# tpa6120a2_headamp.net
KiCad netlist of a schematic drawn in EAGLE
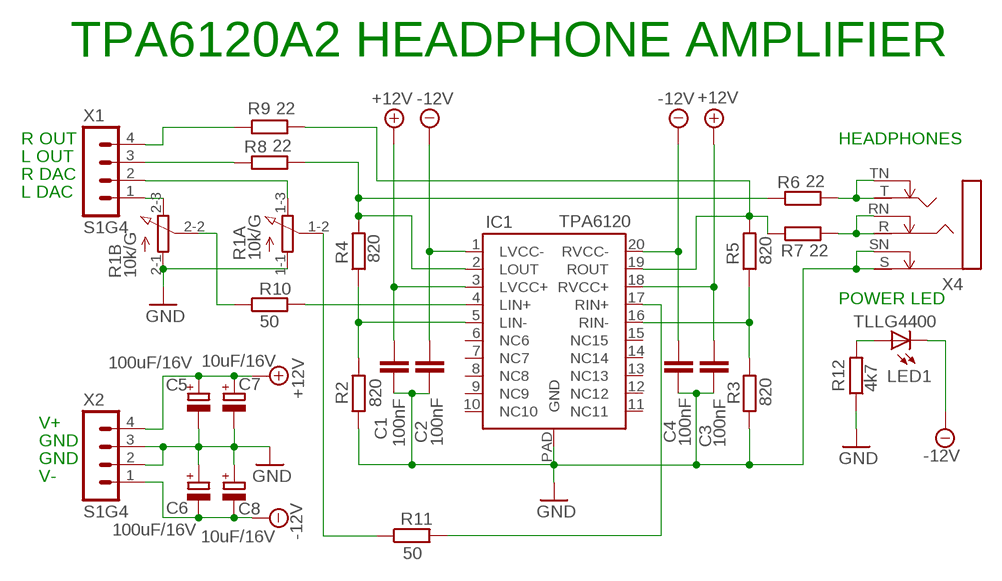
[diagram p0: schematic, sheet 1]

(export (version "E")
  (design (tool "Eeschema 10.0.6"))
  (components
    (comp (ref "C1")
      (value "100nF")
      (footprint "eagle-import:C1206")
      (libsource (lib "eagle-import") (part "C-EUC1206"))
    )
    (comp (ref "C2")
      (value "100nF")
      (footprint "eagle-import:C1206")
      (libsource (lib "eagle-import") (part "C-EUC1206"))
    )
    (comp (ref "C3")
      (value "100nF")
      (footprint "eagle-import:C1206")
      (libsource (lib "eagle-import") (part "C-EUC1206"))
    )
    (comp (ref "C4")
      (value "100nF")
      (footprint "eagle-import:C1206")
      (libsource (lib "eagle-import") (part "C-EUC1206"))
    )
    (comp (ref "C5")
      (value "100uF/16V")
      (footprint "eagle-import:SMC_D")
      (libsource (lib "eagle-import") (part "CPOL-EUSMCD"))
    )
    (comp (ref "C6")
      (value "100uF/16V")
      (footprint "eagle-import:SMC_D")
      (libsource (lib "eagle-import") (part "CPOL-EUSMCD"))
    )
    (comp (ref "C7")
      (value "10uF/16V")
      (footprint "eagle-import:SMC_C")
      (libsource (lib "eagle-import") (part "CPOL-EUSMCC"))
    )
    (comp (ref "C8")
      (value "10uF/16V")
      (footprint "eagle-import:SMC_C")
      (libsource (lib "eagle-import") (part "CPOL-EUSMCC"))
    )
    (comp (ref "IC1")
      (value "TPA6120")
      (footprint "eagle-import:SO20POWERPAD")
      (libsource (lib "eagle-import") (part "TPA6120"))
    )
    (comp (ref "LED1")
      (value "TLLG4400")
      (footprint "eagle-import:LED3MM")
      (fields (field (name "MF") "VISHAY SEMICONDUCTOR"))
      (libsource (lib "eagle-import") (part "TLLG4400"))
    )
    (comp (ref "R1")
      (value "10k/G")
      (footprint "eagle-import:ALPS-RK27-DUAL")
      (libsource (lib "eagle-import") (part "ALPS-RK27-DUAL"))
    )
    (comp (ref "R2")
      (value "820")
      (footprint "eagle-import:R1206")
      (libsource (lib "eagle-import") (part "R-EU_R1206"))
    )
    (comp (ref "R3")
      (value "820")
      (footprint "eagle-import:R1206")
      (libsource (lib "eagle-import") (part "R-EU_R1206"))
    )
    (comp (ref "R4")
      (value "820")
      (footprint "eagle-import:R1206")
      (libsource (lib "eagle-import") (part "R-EU_R1206"))
    )
    (comp (ref "R5")
      (value "820")
      (footprint "eagle-import:R1206")
      (libsource (lib "eagle-import") (part "R-EU_R1206"))
    )
    (comp (ref "R6")
      (value "22")
      (footprint "eagle-import:R1206")
      (libsource (lib "eagle-import") (part "R-EU_R1206"))
    )
    (comp (ref "R7")
      (value "22")
      (footprint "eagle-import:R1206")
      (libsource (lib "eagle-import") (part "R-EU_R1206"))
    )
    (comp (ref "R8")
      (value "22")
      (footprint "eagle-import:R1206")
      (libsource (lib "eagle-import") (part "R-EU_R1206"))
    )
    (comp (ref "R9")
      (value "22")
      (footprint "eagle-import:R1206")
      (libsource (lib "eagle-import") (part "R-EU_R1206"))
    )
    (comp (ref "R10")
      (value "50")
      (footprint "eagle-import:R1206")
      (libsource (lib "eagle-import") (part "R-EU_R1206"))
    )
    (comp (ref "R11")
      (value "50")
      (footprint "eagle-import:R1206")
      (libsource (lib "eagle-import") (part "R-EU_R1206"))
    )
    (comp (ref "R12")
      (value "4k7")
      (footprint "eagle-import:R1206")
      (libsource (lib "eagle-import") (part "R-EU_R1206"))
    )
    (comp (ref "X1")
      (value "S1G4")
      (footprint "eagle-import:MA04-1")
      (libsource (lib "eagle-import") (part "MA04-1"))
    )
    (comp (ref "X2")
      (value "S1G4")
      (footprint "eagle-import:MA04-1")
      (libsource (lib "eagle-import") (part "MA04-1"))
    )
    (comp (ref "X4")
      (value "NMJ6HCD2")
      (footprint "eagle-import:NMJ6HCD2")
      (libsource (lib "eagle-import") (part "NMJ6HCD2"))
    )
  )
  (nets
    (net (code "1") (name "+12V") (class "Default")
      (node (ref "C1") (pin "1") (pinfunction "1_1") (pintype "passive"))
      (node (ref "C3") (pin "1") (pinfunction "1_1") (pintype "passive"))
      (node (ref "C5") (pin "+") (pinfunction "+_+") (pintype "passive"))
      (node (ref "C7") (pin "+") (pinfunction "+_+") (pintype "passive"))
      (node (ref "IC1") (pin "18") (pinfunction "RVCC+_18") (pintype "power_in"))
      (node (ref "IC1") (pin "3") (pinfunction "LVCC+_3") (pintype "power_in"))
      (node (ref "X2") (pin "4") (pinfunction "4_4") (pintype "passive"))
    )
    (net (code "2") (name "-12V") (class "Default")
      (node (ref "C2") (pin "1") (pinfunction "1_1") (pintype "passive"))
      (node (ref "C4") (pin "1") (pinfunction "1_1") (pintype "passive"))
      (node (ref "C6") (pin "-") (pinfunction "-_-") (pintype "passive"))
      (node (ref "C8") (pin "-") (pinfunction "-_-") (pintype "passive"))
      (node (ref "IC1") (pin "1") (pinfunction "LVCC-_1") (pintype "power_in"))
      (node (ref "IC1") (pin "20") (pinfunction "RVCC-_20") (pintype "power_in"))
      (node (ref "LED1") (pin "K") (pinfunction "C_K") (pintype "passive"))
      (node (ref "X2") (pin "1") (pinfunction "1_1") (pintype "passive"))
    )
    (net (code "3") (name "GND") (class "Default")
      (node (ref "C1") (pin "2") (pinfunction "2_2") (pintype "passive"))
      (node (ref "C2") (pin "2") (pinfunction "2_2") (pintype "passive"))
      (node (ref "C3") (pin "2") (pinfunction "2_2") (pintype "passive"))
      (node (ref "C4") (pin "2") (pinfunction "2_2") (pintype "passive"))
      (node (ref "C5") (pin "-") (pinfunction "-_-") (pintype "passive"))
      (node (ref "C6") (pin "+") (pinfunction "+_+") (pintype "passive"))
      (node (ref "C7") (pin "-") (pinfunction "-_-") (pintype "passive"))
      (node (ref "C8") (pin "+") (pinfunction "+_+") (pintype "passive"))
      (node (ref "IC1") (pin "PAD") (pinfunction "GND_PAD") (pintype "power_in"))
      (node (ref "R1") (pin "1-1") (pinfunction "1_1-1") (pintype "passive"))
      (node (ref "R1") (pin "2-1") (pinfunction "1_2-1") (pintype "passive"))
      (node (ref "R12") (pin "1") (pinfunction "1_1") (pintype "passive"))
      (node (ref "R2") (pin "1") (pinfunction "1_1") (pintype "passive"))
      (node (ref "R3") (pin "1") (pinfunction "1_1") (pintype "passive"))
      (node (ref "X2") (pin "2") (pinfunction "2_2") (pintype "passive"))
      (node (ref "X2") (pin "3") (pinfunction "3_3") (pintype "passive"))
      (node (ref "X4") (pin "S") (pinfunction "S_S") (pintype "passive"))
      (node (ref "X4") (pin "SN") (pinfunction "SN_SN") (pintype "passive"))
    )
    (net (code "4") (name "Net-(IC1-LIN+)") (class "Default")
      (node (ref "IC1") (pin "4") (pinfunction "LIN+_4") (pintype "input"))
      (node (ref "R10") (pin "2") (pinfunction "2_2") (pintype "passive"))
    )
    (net (code "5") (name "Net-(IC1-LIN-)") (class "Default")
      (node (ref "IC1") (pin "5") (pinfunction "LIN-_5") (pintype "input"))
      (node (ref "R2") (pin "2") (pinfunction "2_2") (pintype "passive"))
      (node (ref "R4") (pin "1") (pinfunction "1_1") (pintype "passive"))
    )
    (net (code "6") (name "Net-(IC1-LOUT)") (class "Default")
      (node (ref "IC1") (pin "2") (pinfunction "LOUT_2") (pintype "output"))
      (node (ref "R4") (pin "2") (pinfunction "2_2") (pintype "passive"))
      (node (ref "R6") (pin "1") (pinfunction "1_1") (pintype "passive"))
      (node (ref "R8") (pin "2") (pinfunction "2_2") (pintype "passive"))
    )
    (net (code "7") (name "Net-(IC1-RIN+)") (class "Default")
      (node (ref "IC1") (pin "17") (pinfunction "RIN+_17") (pintype "input"))
      (node (ref "R11") (pin "2") (pinfunction "2_2") (pintype "passive"))
    )
    (net (code "8") (name "Net-(IC1-RIN-)") (class "Default")
      (node (ref "IC1") (pin "16") (pinfunction "RIN-_16") (pintype "input"))
      (node (ref "R3") (pin "2") (pinfunction "2_2") (pintype "passive"))
      (node (ref "R5") (pin "1") (pinfunction "1_1") (pintype "passive"))
    )
    (net (code "9") (name "Net-(IC1-ROUT)") (class "Default")
      (node (ref "IC1") (pin "19") (pinfunction "ROUT_19") (pintype "output"))
      (node (ref "R5") (pin "2") (pinfunction "2_2") (pintype "passive"))
      (node (ref "R7") (pin "1") (pinfunction "1_1") (pintype "passive"))
      (node (ref "R9") (pin "2") (pinfunction "2_2") (pintype "passive"))
    )
    (net (code "10") (name "Net-(LED1-PadA)") (class "Default")
      (node (ref "LED1") (pin "A") (pinfunction "A_A") (pintype "passive"))
      (node (ref "R12") (pin "2") (pinfunction "2_2") (pintype "passive"))
    )
    (net (code "11") (name "Net-(R1A-2)") (class "Default")
      (node (ref "R1") (pin "1-2") (pinfunction "2_1-2") (pintype "passive"))
      (node (ref "R11") (pin "1") (pinfunction "1_1") (pintype "passive"))
    )
    (net (code "12") (name "Net-(R1A-3)") (class "Default")
      (node (ref "R1") (pin "1-3") (pinfunction "3_1-3") (pintype "passive"))
      (node (ref "X1") (pin "2") (pinfunction "2_2") (pintype "passive"))
    )
    (net (code "13") (name "Net-(R1B-2)") (class "Default")
      (node (ref "R1") (pin "2-2") (pinfunction "2_2-2") (pintype "passive"))
      (node (ref "R10") (pin "1") (pinfunction "1_1") (pintype "passive"))
    )
    (net (code "14") (name "Net-(R1B-3)") (class "Default")
      (node (ref "R1") (pin "2-3") (pinfunction "3_2-3") (pintype "passive"))
      (node (ref "X1") (pin "1") (pinfunction "1_1") (pintype "passive"))
    )
    (net (code "15") (name "Net-(R6-Pad2)") (class "Default")
      (node (ref "R6") (pin "2") (pinfunction "2_2") (pintype "passive"))
      (node (ref "X4") (pin "T") (pinfunction "T_T") (pintype "passive"))
      (node (ref "X4") (pin "TN") (pinfunction "TN_TN") (pintype "passive"))
    )
    (net (code "16") (name "Net-(R7-Pad2)") (class "Default")
      (node (ref "R7") (pin "2") (pinfunction "2_2") (pintype "passive"))
      (node (ref "X4") (pin "R") (pinfunction "R_R") (pintype "passive"))
      (node (ref "X4") (pin "RN") (pinfunction "RN_RN") (pintype "passive"))
    )
    (net (code "17") (name "Net-(R8-Pad1)") (class "Default")
      (node (ref "R8") (pin "1") (pinfunction "1_1") (pintype "passive"))
      (node (ref "X1") (pin "3") (pinfunction "3_3") (pintype "passive"))
    )
    (net (code "18") (name "Net-(R9-Pad1)") (class "Default")
      (node (ref "R9") (pin "1") (pinfunction "1_1") (pintype "passive"))
      (node (ref "X1") (pin "4") (pinfunction "4_4") (pintype "passive"))
    )
    (net (code "19") (name "unconnected-(IC1-NC6-Pad6)") (class "Default")
      (node (ref "IC1") (pin "6") (pinfunction "NC6_6") (pintype "no_connect"))
    )
    (net (code "20") (name "unconnected-(IC1-NC7-Pad7)") (class "Default")
      (node (ref "IC1") (pin "7") (pinfunction "NC7_7") (pintype "no_connect"))
    )
    (net (code "21") (name "unconnected-(IC1-NC8-Pad8)") (class "Default")
      (node (ref "IC1") (pin "8") (pinfunction "NC8_8") (pintype "no_connect"))
    )
    (net (code "22") (name "unconnected-(IC1-NC9-Pad9)") (class "Default")
      (node (ref "IC1") (pin "9") (pinfunction "NC9_9") (pintype "no_connect"))
    )
    (net (code "23") (name "unconnected-(IC1-NC10-Pad10)") (class "Default")
      (node (ref "IC1") (pin "10") (pinfunction "NC10_10") (pintype "no_connect"))
    )
    (net (code "24") (name "unconnected-(IC1-NC11-Pad11)") (class "Default")
      (node (ref "IC1") (pin "11") (pinfunction "NC11_11") (pintype "no_connect"))
    )
    (net (code "25") (name "unconnected-(IC1-NC12-Pad12)") (class "Default")
      (node (ref "IC1") (pin "12") (pinfunction "NC12_12") (pintype "no_connect"))
    )
    (net (code "26") (name "unconnected-(IC1-NC13-Pad13)") (class "Default")
      (node (ref "IC1") (pin "13") (pinfunction "NC13_13") (pintype "no_connect"))
    )
    (net (code "27") (name "unconnected-(IC1-NC14-Pad14)") (class "Default")
      (node (ref "IC1") (pin "14") (pinfunction "NC14_14") (pintype "no_connect"))
    )
    (net (code "28") (name "unconnected-(IC1-NC15-Pad15)") (class "Default")
      (node (ref "IC1") (pin "15") (pinfunction "NC15_15") (pintype "no_connect"))
    )
  )
)
